# Sensor3.net
KiCad netlist of a schematic drawn in EAGLE
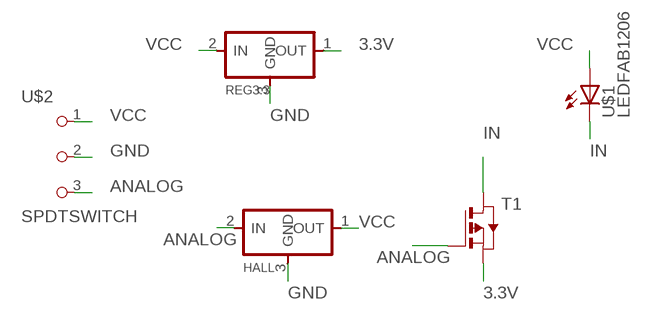
[diagram p0: schematic, sheet 1]

(export (version "E")
  (design (tool "Eeschema 10.0.6"))
  (components
    (comp (ref "HALL")
      (value "REGULATORSOT23")
      (footprint "eagle-import:SOT23")
      (libsource (lib "eagle-import") (part "REGULATORSOT23"))
    )
    (comp (ref "REG3.3")
      (value "REGULATORSOT23")
      (footprint "eagle-import:SOT23")
      (libsource (lib "eagle-import") (part "REGULATORSOT23"))
    )
    (comp (ref "T1")
      (value "PMOSFETSOT23")
      (footprint "eagle-import:SOT-23")
      (libsource (lib "eagle-import") (part "PMOSFETSOT23"))
    )
    (comp (ref "U$1")
      (value "LEDFAB1206")
      (footprint "eagle-import:LED1206FAB")
      (libsource (lib "eagle-import") (part "LEDFAB1206"))
    )
    (comp (ref "U$2")
      (value "SPDTSWITCH")
      (footprint "eagle-import:SPDTSWITCH")
      (libsource (lib "eagle-import") (part "SPDTSWITCH"))
    )
  )
  (nets
    (net (code "1") (name "/3.3V") (class "Default")
      (node (ref "REG3.3") (pin "1") (pinfunction "OUT_1") (pintype "bidirectional"))
      (node (ref "T1") (pin "2") (pinfunction "S_2") (pintype "passive"))
    )
    (net (code "2") (name "/ANALOG") (class "Default")
      (node (ref "HALL") (pin "2") (pinfunction "IN_2") (pintype "bidirectional"))
      (node (ref "T1") (pin "3") (pinfunction "G_3") (pintype "passive"))
      (node (ref "U$2") (pin "3") (pinfunction "3_3") (pintype "passive"))
    )
    (net (code "3") (name "/GND") (class "Default")
      (node (ref "HALL") (pin "3") (pinfunction "GND_3") (pintype "bidirectional"))
      (node (ref "REG3.3") (pin "3") (pinfunction "GND_3") (pintype "bidirectional"))
      (node (ref "U$2") (pin "2") (pinfunction "2_2") (pintype "passive"))
    )
    (net (code "4") (name "/IN") (class "Default")
      (node (ref "T1") (pin "1") (pinfunction "D_1") (pintype "passive"))
      (node (ref "U$1") (pin "2") (pinfunction "C_2") (pintype "passive"))
    )
    (net (code "5") (name "/VCC") (class "Default")
      (node (ref "HALL") (pin "1") (pinfunction "OUT_1") (pintype "bidirectional"))
      (node (ref "REG3.3") (pin "2") (pinfunction "IN_2") (pintype "bidirectional"))
      (node (ref "U$1") (pin "1") (pinfunction "A_1") (pintype "passive"))
      (node (ref "U$2") (pin "1") (pinfunction "1_1") (pintype "passive"))
    )
  )
)
